# controller_board.net
KiCad netlist of a schematic drawn in EAGLE
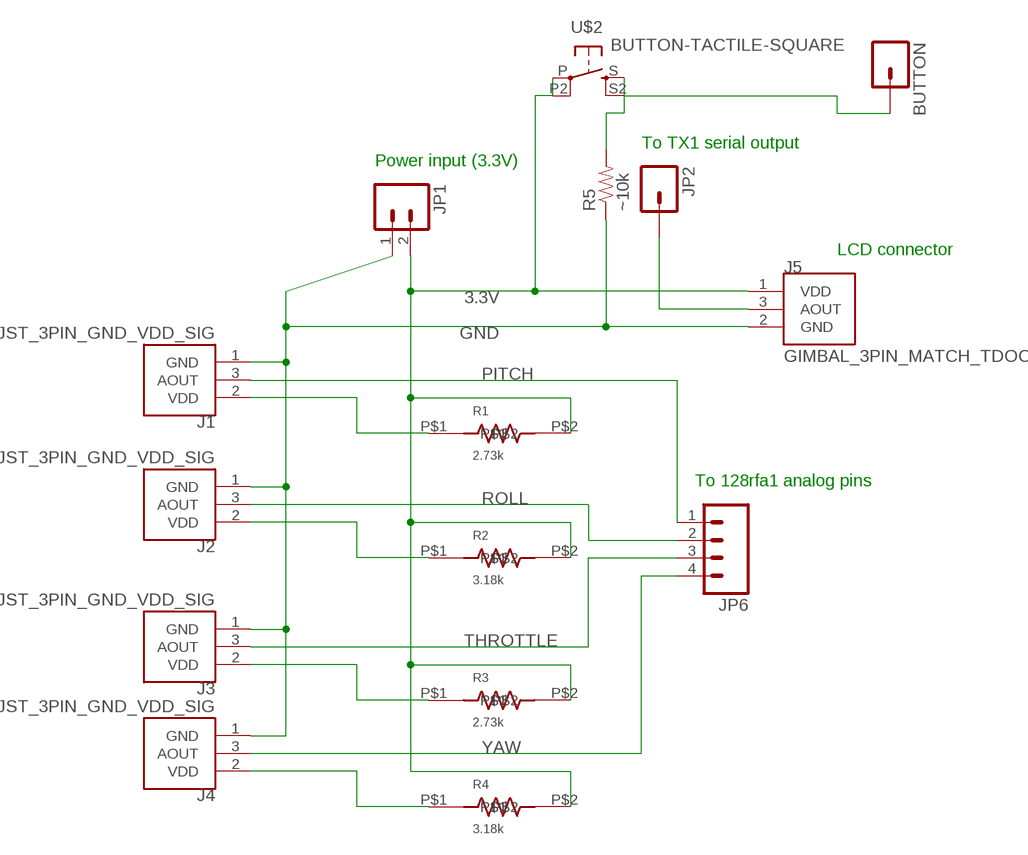
[diagram p0: schematic, sheet 1]

(export (version "E")
  (design (tool "Eeschema 10.0.6"))
  (components
    (comp (ref "BUTTON")
      (value "M01PTH")
      (footprint "eagle-import:1X01")
      (libsource (lib "eagle-import") (part "M01PTH"))
    )
    (comp (ref "J1")
      (value "JST_3PIN_GND_VDD_SIG")
      (footprint "eagle-import:JST-3-PTH-REVERSE")
      (libsource (lib "eagle-import") (part "JST_3PIN_GND_VDD_SIG"))
    )
    (comp (ref "J2")
      (value "JST_3PIN_GND_VDD_SIG")
      (footprint "eagle-import:JST-3-PTH-REVERSE")
      (libsource (lib "eagle-import") (part "JST_3PIN_GND_VDD_SIG"))
    )
    (comp (ref "J3")
      (value "JST_3PIN_GND_VDD_SIG")
      (footprint "eagle-import:JST-3-PTH-REVERSE")
      (libsource (lib "eagle-import") (part "JST_3PIN_GND_VDD_SIG"))
    )
    (comp (ref "J4")
      (value "JST_3PIN_GND_VDD_SIG")
      (footprint "eagle-import:JST-3-PTH-REVERSE")
      (libsource (lib "eagle-import") (part "JST_3PIN_GND_VDD_SIG"))
    )
    (comp (ref "J5")
      (value "GIMBAL_3PIN_MATCH_TDOCU")
      (footprint "eagle-import:JST-3-PTH")
      (libsource (lib "eagle-import") (part "GIMBAL_3PIN_MATCH_TDOCU"))
    )
    (comp (ref "JP1")
      (value "M021X02_NO_SILK")
      (footprint "eagle-import:1X02_NO_SILK")
      (libsource (lib "eagle-import") (part "M021X02_NO_SILK"))
    )
    (comp (ref "JP2")
      (value "M01PTH")
      (footprint "eagle-import:1X01")
      (libsource (lib "eagle-import") (part "M01PTH"))
    )
    (comp (ref "JP6")
      (value "M04PTH")
      (footprint "eagle-import:1X04")
      (libsource (lib "eagle-import") (part "M04PTH"))
    )
    (comp (ref "R1")
      (value "2.73k")
      (footprint "eagle-import:CRF12")
      (fields (field (name "CREATOR") "Daniel Knapp"))
      (libsource (lib "eagle-import") (part "RESISTOR-THROUGH_HOLE"))
    )
    (comp (ref "R2")
      (value "3.18k")
      (footprint "eagle-import:CRF12")
      (fields (field (name "CREATOR") "Daniel Knapp"))
      (libsource (lib "eagle-import") (part "RESISTOR-THROUGH_HOLE"))
    )
    (comp (ref "R3")
      (value "2.73k")
      (footprint "eagle-import:CRF12")
      (fields (field (name "CREATOR") "Daniel Knapp"))
      (libsource (lib "eagle-import") (part "RESISTOR-THROUGH_HOLE"))
    )
    (comp (ref "R4")
      (value "3.18k")
      (footprint "eagle-import:CRF12")
      (fields (field (name "CREATOR") "Daniel Knapp"))
      (libsource (lib "eagle-import") (part "RESISTOR-THROUGH_HOLE"))
    )
    (comp (ref "R5")
      (value "~10k")
      (footprint "eagle-import:AXIAL-0.4")
      (libsource (lib "eagle-import") (part "RESISTORPTH-1/4W"))
    )
    (comp (ref "U$2")
      (value "BUTTON-TACTILE-SQUARE")
      (footprint "eagle-import:BUTTON-TACTILE-SQUARE-ADAFRUIT1010")
      (libsource (lib "eagle-import") (part "BUTTON-TACTILE-SQUARE"))
    )
  )
  (nets
    (net (code "1") (name "/3.3V") (class "Default")
      (node (ref "J5") (pin "1") (pinfunction "VDD_1") (pintype "power_in"))
      (node (ref "JP1") (pin "2") (pinfunction "2_2") (pintype "passive"))
      (node (ref "R1") (pin "P$2") (pinfunction "P$2_P$2") (pintype "bidirectional"))
      (node (ref "R2") (pin "P$2") (pinfunction "P$2_P$2") (pintype "bidirectional"))
      (node (ref "R3") (pin "P$2") (pinfunction "P$2_P$2") (pintype "bidirectional"))
      (node (ref "R4") (pin "P$2") (pinfunction "P$2_P$2") (pintype "bidirectional"))
      (node (ref "U$2") (pin "P") (pinfunction "P_P") (pintype "passive"))
      (node (ref "U$2") (pin "P2") (pinfunction "P1_P2") (pintype "passive"))
    )
    (net (code "2") (name "/GND") (class "Default")
      (node (ref "J1") (pin "1") (pinfunction "GND_1") (pintype "power_in"))
      (node (ref "J2") (pin "1") (pinfunction "GND_1") (pintype "power_in"))
      (node (ref "J3") (pin "1") (pinfunction "GND_1") (pintype "power_in"))
      (node (ref "J4") (pin "1") (pinfunction "GND_1") (pintype "power_in"))
      (node (ref "J5") (pin "2") (pinfunction "GND_2") (pintype "power_in"))
      (node (ref "JP1") (pin "1") (pinfunction "1_1") (pintype "passive"))
      (node (ref "R5") (pin "P$1") (pinfunction "1_P$1") (pintype "passive"))
    )
    (net (code "3") (name "/PITCH") (class "Default")
      (node (ref "J1") (pin "3") (pinfunction "AOUT_3") (pintype "bidirectional"))
      (node (ref "JP6") (pin "1") (pinfunction "1_1") (pintype "passive"))
    )
    (net (code "4") (name "/ROLL") (class "Default")
      (node (ref "J2") (pin "3") (pinfunction "AOUT_3") (pintype "bidirectional"))
      (node (ref "JP6") (pin "2") (pinfunction "2_2") (pintype "passive"))
    )
    (net (code "5") (name "/THROTTLE") (class "Default")
      (node (ref "J3") (pin "3") (pinfunction "AOUT_3") (pintype "bidirectional"))
      (node (ref "JP6") (pin "3") (pinfunction "3_3") (pintype "passive"))
    )
    (net (code "6") (name "/YAW") (class "Default")
      (node (ref "J4") (pin "3") (pinfunction "AOUT_3") (pintype "bidirectional"))
      (node (ref "JP6") (pin "4") (pinfunction "4_4") (pintype "passive"))
    )
    (net (code "7") (name "Net-(J1-VDD)") (class "Default")
      (node (ref "J1") (pin "2") (pinfunction "VDD_2") (pintype "power_in"))
      (node (ref "R1") (pin "P$1") (pinfunction "P$1_P$1") (pintype "bidirectional"))
    )
    (net (code "8") (name "Net-(J2-VDD)") (class "Default")
      (node (ref "J2") (pin "2") (pinfunction "VDD_2") (pintype "power_in"))
      (node (ref "R2") (pin "P$1") (pinfunction "P$1_P$1") (pintype "bidirectional"))
    )
    (net (code "9") (name "Net-(J3-VDD)") (class "Default")
      (node (ref "J3") (pin "2") (pinfunction "VDD_2") (pintype "power_in"))
      (node (ref "R3") (pin "P$1") (pinfunction "P$1_P$1") (pintype "bidirectional"))
    )
    (net (code "10") (name "Net-(J4-VDD)") (class "Default")
      (node (ref "J4") (pin "2") (pinfunction "VDD_2") (pintype "power_in"))
      (node (ref "R4") (pin "P$1") (pinfunction "P$1_P$1") (pintype "bidirectional"))
    )
    (net (code "11") (name "Net-(J5-AOUT)") (class "Default")
      (node (ref "J5") (pin "3") (pinfunction "AOUT_3") (pintype "bidirectional"))
      (node (ref "JP2") (pin "1") (pinfunction "1_1") (pintype "passive"))
    )
    (net (code "12") (name "Net-(R5-2)") (class "Default")
      (node (ref "BUTTON") (pin "1") (pinfunction "1_1") (pintype "passive"))
      (node (ref "R5") (pin "P$2") (pinfunction "2_P$2") (pintype "passive"))
      (node (ref "U$2") (pin "S") (pinfunction "S_S") (pintype "passive"))
      (node (ref "U$2") (pin "S2") (pinfunction "S1_S2") (pintype "passive"))
    )
  )
)
